# Adafruit_TLC5947.net
KiCad netlist of a schematic drawn in EAGLE
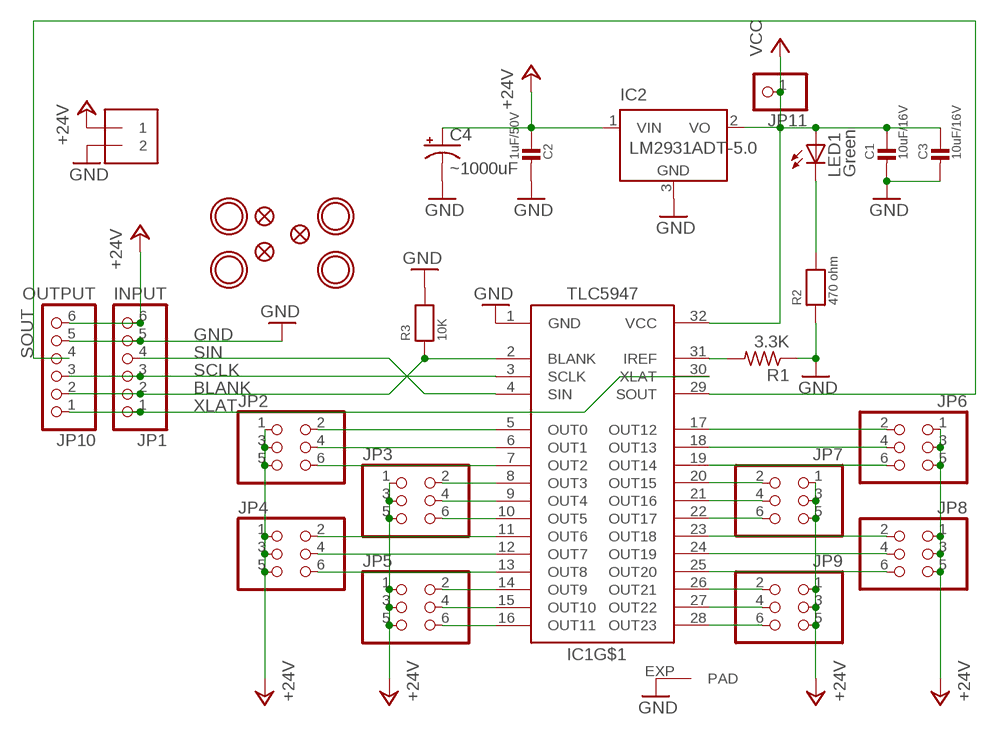
[diagram p0: schematic, sheet 1]

(export (version "E")
  (design (tool "Eeschema 10.0.6"))
  (components
    (comp (ref "C1")
      (value "10uF/16V")
      (footprint "eagle-import:0805")
      (libsource (lib "eagle-import") (part "CAP_CERAMIC0805"))
    )
    (comp (ref "C2")
      (value "1uF/50V")
      (footprint "eagle-import:0805")
      (libsource (lib "eagle-import") (part "CAP_CERAMIC0805"))
    )
    (comp (ref "C3")
      (value "10uF/16V")
      (footprint "eagle-import:0805")
      (libsource (lib "eagle-import") (part "CAP_CERAMIC0805"))
    )
    (comp (ref "C4")
      (value "~1000uF")
      (footprint "eagle-import:E3,5-8")
      (libsource (lib "eagle-import") (part "CPOL-USE3.5-8"))
    )
    (comp (ref "FID1")
      (value "FIDUCIAL\"\"")
      (footprint "eagle-import:FIDUCIAL_1MM")
      (libsource (lib "eagle-import") (part "FIDUCIAL{dblquote}{dblquote}"))
    )
    (comp (ref "FID2")
      (value "FIDUCIAL\"\"")
      (footprint "eagle-import:FIDUCIAL_1MM")
      (libsource (lib "eagle-import") (part "FIDUCIAL{dblquote}{dblquote}"))
    )
    (comp (ref "FID3")
      (value "FIDUCIAL\"\"")
      (footprint "eagle-import:FIDUCIAL_1MM")
      (libsource (lib "eagle-import") (part "FIDUCIAL{dblquote}{dblquote}"))
    )
    (comp (ref "IC1")
      (value "TLC5947-DAP")
      (footprint "eagle-import:HTSSOP32DAP")
      (libsource (lib "eagle-import") (part "TLC5947-DAP"))
    )
    (comp (ref "IC2")
      (value "LM2931ADT-5.0")
      (footprint "eagle-import:TO252")
      (fields (field (name "MPN") "LM2936DT-3.3."))
      (libsource (lib "eagle-import") (part "LM2936?DT-3.3"))
    )
    (comp (ref "J1")
      (value "1X2-3.5MM")
      (footprint "eagle-import:1X2-3.5MM")
      (libsource (lib "eagle-import") (part "1X2-3.5MM"))
    )
    (comp (ref "JP1")
      (value "INPUT")
      (footprint "eagle-import:1X06-CLEANBIG")
      (libsource (lib "eagle-import") (part "PINHD-1X6CB"))
    )
    (comp (ref "JP2")
      (value "HEADER-2X3")
      (footprint "eagle-import:2X03_ROUND_70MIL")
      (libsource (lib "eagle-import") (part "HEADER-2X3"))
    )
    (comp (ref "JP3")
      (value "HEADER-2X3")
      (footprint "eagle-import:2X03_ROUND_70MIL")
      (libsource (lib "eagle-import") (part "HEADER-2X3"))
    )
    (comp (ref "JP4")
      (value "HEADER-2X3")
      (footprint "eagle-import:2X03_ROUND_70MIL")
      (libsource (lib "eagle-import") (part "HEADER-2X3"))
    )
    (comp (ref "JP5")
      (value "HEADER-2X3")
      (footprint "eagle-import:2X03_ROUND_70MIL")
      (libsource (lib "eagle-import") (part "HEADER-2X3"))
    )
    (comp (ref "JP6")
      (value "HEADER-2X3")
      (footprint "eagle-import:2X03_ROUND_70MIL")
      (libsource (lib "eagle-import") (part "HEADER-2X3"))
    )
    (comp (ref "JP7")
      (value "HEADER-2X3")
      (footprint "eagle-import:2X03_ROUND_70MIL")
      (libsource (lib "eagle-import") (part "HEADER-2X3"))
    )
    (comp (ref "JP8")
      (value "HEADER-2X3")
      (footprint "eagle-import:2X03_ROUND_70MIL")
      (libsource (lib "eagle-import") (part "HEADER-2X3"))
    )
    (comp (ref "JP9")
      (value "HEADER-2X3")
      (footprint "eagle-import:2X03_ROUND_70MIL")
      (libsource (lib "eagle-import") (part "HEADER-2X3"))
    )
    (comp (ref "JP10")
      (value "OUTPUT")
      (footprint "eagle-import:1X06-CLEANBIG")
      (libsource (lib "eagle-import") (part "PINHD-1X6CB"))
    )
    (comp (ref "JP11")
      (value "PINHD-1X1CB")
      (footprint "eagle-import:1X01-CLEANBIG")
      (libsource (lib "eagle-import") (part "PINHD-1X1CB"))
    )
    (comp (ref "LED1")
      (value "Green")
      (footprint "eagle-import:CHIP-LED0805")
      (libsource (lib "eagle-import") (part "LEDCHIP-LED0805"))
    )
    (comp (ref "R1")
      (value "3.3K")
      (footprint "eagle-import:0805-THM")
      (libsource (lib "eagle-import") (part "FLIPFLOP-RES"))
    )
    (comp (ref "R2")
      (value "470 ohm")
      (footprint "eagle-import:0805")
      (libsource (lib "eagle-import") (part "RESISTOR0805"))
    )
    (comp (ref "R3")
      (value "10K")
      (footprint "eagle-import:0805")
      (libsource (lib "eagle-import") (part "RESISTOR0805"))
    )
    (comp (ref "U$1")
      (value "MOUNTINGHOLE2.5")
      (footprint "eagle-import:MOUNTINGHOLE_2.5_PLATED")
      (libsource (lib "eagle-import") (part "MOUNTINGHOLE2.5"))
    )
    (comp (ref "U$2")
      (value "MOUNTINGHOLE2.5")
      (footprint "eagle-import:MOUNTINGHOLE_2.5_PLATED")
      (libsource (lib "eagle-import") (part "MOUNTINGHOLE2.5"))
    )
    (comp (ref "U$3")
      (value "MOUNTINGHOLE2.5")
      (footprint "eagle-import:MOUNTINGHOLE_2.5_PLATED")
      (libsource (lib "eagle-import") (part "MOUNTINGHOLE2.5"))
    )
    (comp (ref "U$4")
      (value "MOUNTINGHOLE2.5")
      (footprint "eagle-import:MOUNTINGHOLE_2.5_PLATED")
      (libsource (lib "eagle-import") (part "MOUNTINGHOLE2.5"))
    )
  )
  (nets
    (net (code "1") (name "+24V") (class "Default")
      (node (ref "C2") (pin "1") (pinfunction "P$1_1") (pintype "passive"))
      (node (ref "C4") (pin "+") (pinfunction "+_+") (pintype "passive"))
      (node (ref "IC2") (pin "1") (pinfunction "VIN_1") (pintype "input"))
      (node (ref "J1") (pin "1") (pinfunction "1_1") (pintype "passive"))
      (node (ref "JP1") (pin "6") (pinfunction "6_6") (pintype "passive"))
      (node (ref "JP10") (pin "6") (pinfunction "6_6") (pintype "passive"))
      (node (ref "JP2") (pin "1") (pinfunction "1_1") (pintype "passive"))
      (node (ref "JP2") (pin "3") (pinfunction "3_3") (pintype "passive"))
      (node (ref "JP2") (pin "5") (pinfunction "5_5") (pintype "passive"))
      (node (ref "JP3") (pin "1") (pinfunction "1_1") (pintype "passive"))
      (node (ref "JP3") (pin "3") (pinfunction "3_3") (pintype "passive"))
      (node (ref "JP3") (pin "5") (pinfunction "5_5") (pintype "passive"))
      (node (ref "JP4") (pin "1") (pinfunction "1_1") (pintype "passive"))
      (node (ref "JP4") (pin "3") (pinfunction "3_3") (pintype "passive"))
      (node (ref "JP4") (pin "5") (pinfunction "5_5") (pintype "passive"))
      (node (ref "JP5") (pin "1") (pinfunction "1_1") (pintype "passive"))
      (node (ref "JP5") (pin "3") (pinfunction "3_3") (pintype "passive"))
      (node (ref "JP5") (pin "5") (pinfunction "5_5") (pintype "passive"))
      (node (ref "JP6") (pin "1") (pinfunction "1_1") (pintype "passive"))
      (node (ref "JP6") (pin "3") (pinfunction "3_3") (pintype "passive"))
      (node (ref "JP6") (pin "5") (pinfunction "5_5") (pintype "passive"))
      (node (ref "JP7") (pin "1") (pinfunction "1_1") (pintype "passive"))
      (node (ref "JP7") (pin "3") (pinfunction "3_3") (pintype "passive"))
      (node (ref "JP7") (pin "5") (pinfunction "5_5") (pintype "passive"))
      (node (ref "JP8") (pin "1") (pinfunction "1_1") (pintype "passive"))
      (node (ref "JP8") (pin "3") (pinfunction "3_3") (pintype "passive"))
      (node (ref "JP8") (pin "5") (pinfunction "5_5") (pintype "passive"))
      (node (ref "JP9") (pin "1") (pinfunction "1_1") (pintype "passive"))
      (node (ref "JP9") (pin "3") (pinfunction "3_3") (pintype "passive"))
      (node (ref "JP9") (pin "5") (pinfunction "5_5") (pintype "passive"))
    )
    (net (code "2") (name "/BLANK") (class "Default")
      (node (ref "IC1") (pin "2") (pinfunction "BLANK_2") (pintype "input"))
      (node (ref "JP1") (pin "2") (pinfunction "2_2") (pintype "passive"))
      (node (ref "JP10") (pin "2") (pinfunction "2_2") (pintype "passive"))
      (node (ref "R3") (pin "1") (pinfunction "1_1") (pintype "passive"))
    )
    (net (code "3") (name "/SCLK") (class "Default")
      (node (ref "IC1") (pin "3") (pinfunction "SCLK_3") (pintype "input"))
      (node (ref "JP1") (pin "3") (pinfunction "3_3") (pintype "passive"))
      (node (ref "JP10") (pin "3") (pinfunction "3_3") (pintype "passive"))
    )
    (net (code "4") (name "/SIN") (class "Default")
      (node (ref "IC1") (pin "4") (pinfunction "SIN_4") (pintype "input"))
      (node (ref "JP1") (pin "4") (pinfunction "4_4") (pintype "passive"))
    )
    (net (code "5") (name "/SOUT") (class "Default")
      (node (ref "IC1") (pin "29") (pinfunction "SOUT_29") (pintype "output"))
      (node (ref "JP10") (pin "4") (pinfunction "4_4") (pintype "passive"))
    )
    (net (code "6") (name "/XLAT") (class "Default")
      (node (ref "IC1") (pin "30") (pinfunction "XLAT_30") (pintype "input"))
      (node (ref "JP1") (pin "1") (pinfunction "1_1") (pintype "passive"))
      (node (ref "JP10") (pin "1") (pinfunction "1_1") (pintype "passive"))
    )
    (net (code "7") (name "GND") (class "Default")
      (node (ref "C1") (pin "2") (pinfunction "P$2_2") (pintype "passive"))
      (node (ref "C2") (pin "2") (pinfunction "P$2_2") (pintype "passive"))
      (node (ref "C3") (pin "2") (pinfunction "P$2_2") (pintype "passive"))
      (node (ref "C4") (pin "-") (pinfunction "-_-") (pintype "passive"))
      (node (ref "IC1") (pin "1") (pinfunction "GND_1") (pintype "power_in"))
      (node (ref "IC1") (pin "EXP") (pinfunction "PAD_EXP") (pintype "passive"))
      (node (ref "IC2") (pin "3") (pinfunction "GND_3") (pintype "passive"))
      (node (ref "J1") (pin "2") (pinfunction "2_2") (pintype "passive"))
      (node (ref "JP1") (pin "5") (pinfunction "5_5") (pintype "passive"))
      (node (ref "JP10") (pin "5") (pinfunction "5_5") (pintype "passive"))
      (node (ref "R1") (pin "1") (pinfunction "1_1") (pintype "passive"))
      (node (ref "R2") (pin "1") (pinfunction "1_1") (pintype "passive"))
      (node (ref "R3") (pin "2") (pinfunction "2_2") (pintype "passive"))
    )
    (net (code "8") (name "Net-(IC1A-IREF)") (class "Default")
      (node (ref "IC1") (pin "31") (pinfunction "IREF_31") (pintype "bidirectional"))
      (node (ref "R1") (pin "2") (pinfunction "2_2") (pintype "passive"))
    )
    (net (code "9") (name "Net-(IC1A-OUT0)") (class "Default")
      (node (ref "IC1") (pin "5") (pinfunction "OUT0_5") (pintype "open_collector"))
      (node (ref "JP2") (pin "2") (pinfunction "2_2") (pintype "passive"))
    )
    (net (code "10") (name "Net-(IC1A-OUT1)") (class "Default")
      (node (ref "IC1") (pin "6") (pinfunction "OUT1_6") (pintype "open_collector"))
      (node (ref "JP2") (pin "4") (pinfunction "4_4") (pintype "passive"))
    )
    (net (code "11") (name "Net-(IC1A-OUT2)") (class "Default")
      (node (ref "IC1") (pin "7") (pinfunction "OUT2_7") (pintype "open_collector"))
      (node (ref "JP2") (pin "6") (pinfunction "6_6") (pintype "passive"))
    )
    (net (code "12") (name "Net-(IC1A-OUT3)") (class "Default")
      (node (ref "IC1") (pin "8") (pinfunction "OUT3_8") (pintype "open_collector"))
      (node (ref "JP3") (pin "2") (pinfunction "2_2") (pintype "passive"))
    )
    (net (code "13") (name "Net-(IC1A-OUT4)") (class "Default")
      (node (ref "IC1") (pin "9") (pinfunction "OUT4_9") (pintype "open_collector"))
      (node (ref "JP3") (pin "4") (pinfunction "4_4") (pintype "passive"))
    )
    (net (code "14") (name "Net-(IC1A-OUT5)") (class "Default")
      (node (ref "IC1") (pin "10") (pinfunction "OUT5_10") (pintype "open_collector"))
      (node (ref "JP3") (pin "6") (pinfunction "6_6") (pintype "passive"))
    )
    (net (code "15") (name "Net-(IC1A-OUT6)") (class "Default")
      (node (ref "IC1") (pin "11") (pinfunction "OUT6_11") (pintype "open_collector"))
      (node (ref "JP4") (pin "2") (pinfunction "2_2") (pintype "passive"))
    )
    (net (code "16") (name "Net-(IC1A-OUT7)") (class "Default")
      (node (ref "IC1") (pin "12") (pinfunction "OUT7_12") (pintype "open_collector"))
      (node (ref "JP4") (pin "4") (pinfunction "4_4") (pintype "passive"))
    )
    (net (code "17") (name "Net-(IC1A-OUT8)") (class "Default")
      (node (ref "IC1") (pin "13") (pinfunction "OUT8_13") (pintype "open_collector"))
      (node (ref "JP4") (pin "6") (pinfunction "6_6") (pintype "passive"))
    )
    (net (code "18") (name "Net-(IC1A-OUT9)") (class "Default")
      (node (ref "IC1") (pin "14") (pinfunction "OUT9_14") (pintype "open_collector"))
      (node (ref "JP5") (pin "2") (pinfunction "2_2") (pintype "passive"))
    )
    (net (code "19") (name "Net-(IC1A-OUT10)") (class "Default")
      (node (ref "IC1") (pin "15") (pinfunction "OUT10_15") (pintype "open_collector"))
      (node (ref "JP5") (pin "4") (pinfunction "4_4") (pintype "passive"))
    )
    (net (code "20") (name "Net-(IC1A-OUT11)") (class "Default")
      (node (ref "IC1") (pin "16") (pinfunction "OUT11_16") (pintype "open_collector"))
      (node (ref "JP5") (pin "6") (pinfunction "6_6") (pintype "passive"))
    )
    (net (code "21") (name "Net-(IC1A-OUT12)") (class "Default")
      (node (ref "IC1") (pin "17") (pinfunction "OUT12_17") (pintype "open_collector"))
      (node (ref "JP6") (pin "2") (pinfunction "2_2") (pintype "passive"))
    )
    (net (code "22") (name "Net-(IC1A-OUT13)") (class "Default")
      (node (ref "IC1") (pin "18") (pinfunction "OUT13_18") (pintype "open_collector"))
      (node (ref "JP6") (pin "4") (pinfunction "4_4") (pintype "passive"))
    )
    (net (code "23") (name "Net-(IC1A-OUT14)") (class "Default")
      (node (ref "IC1") (pin "19") (pinfunction "OUT14_19") (pintype "open_collector"))
      (node (ref "JP6") (pin "6") (pinfunction "6_6") (pintype "passive"))
    )
    (net (code "24") (name "Net-(IC1A-OUT15)") (class "Default")
      (node (ref "IC1") (pin "20") (pinfunction "OUT15_20") (pintype "open_collector"))
      (node (ref "JP7") (pin "2") (pinfunction "2_2") (pintype "passive"))
    )
    (net (code "25") (name "Net-(IC1A-OUT16)") (class "Default")
      (node (ref "IC1") (pin "21") (pinfunction "OUT16_21") (pintype "open_collector"))
      (node (ref "JP7") (pin "4") (pinfunction "4_4") (pintype "passive"))
    )
    (net (code "26") (name "Net-(IC1A-OUT17)") (class "Default")
      (node (ref "IC1") (pin "22") (pinfunction "OUT17_22") (pintype "open_collector"))
      (node (ref "JP7") (pin "6") (pinfunction "6_6") (pintype "passive"))
    )
    (net (code "27") (name "Net-(IC1A-OUT18)") (class "Default")
      (node (ref "IC1") (pin "23") (pinfunction "OUT18_23") (pintype "open_collector"))
      (node (ref "JP8") (pin "2") (pinfunction "2_2") (pintype "passive"))
    )
    (net (code "28") (name "Net-(IC1A-OUT19)") (class "Default")
      (node (ref "IC1") (pin "24") (pinfunction "OUT19_24") (pintype "open_collector"))
      (node (ref "JP8") (pin "4") (pinfunction "4_4") (pintype "passive"))
    )
    (net (code "29") (name "Net-(IC1A-OUT20)") (class "Default")
      (node (ref "IC1") (pin "25") (pinfunction "OUT20_25") (pintype "open_collector"))
      (node (ref "JP8") (pin "6") (pinfunction "6_6") (pintype "passive"))
    )
    (net (code "30") (name "Net-(IC1A-OUT21)") (class "Default")
      (node (ref "IC1") (pin "26") (pinfunction "OUT21_26") (pintype "open_collector"))
      (node (ref "JP9") (pin "2") (pinfunction "2_2") (pintype "passive"))
    )
    (net (code "31") (name "Net-(IC1A-OUT22)") (class "Default")
      (node (ref "IC1") (pin "27") (pinfunction "OUT22_27") (pintype "open_collector"))
      (node (ref "JP9") (pin "4") (pinfunction "4_4") (pintype "passive"))
    )
    (net (code "32") (name "Net-(IC1A-OUT23)") (class "Default")
      (node (ref "IC1") (pin "28") (pinfunction "OUT23_28") (pintype "open_collector"))
      (node (ref "JP9") (pin "6") (pinfunction "6_6") (pintype "passive"))
    )
    (net (code "33") (name "Net-(LED1-PadC)") (class "Default")
      (node (ref "LED1") (pin "C") (pinfunction "C_C") (pintype "passive"))
      (node (ref "R2") (pin "2") (pinfunction "2_2") (pintype "passive"))
    )
    (net (code "34") (name "VCC") (class "Default")
      (node (ref "C1") (pin "1") (pinfunction "P$1_1") (pintype "passive"))
      (node (ref "C3") (pin "1") (pinfunction "P$1_1") (pintype "passive"))
      (node (ref "IC1") (pin "32") (pinfunction "VCC_32") (pintype "power_in"))
      (node (ref "IC2") (pin "2") (pinfunction "VO_2") (pintype "passive"))
      (node (ref "JP11") (pin "1") (pinfunction "1_1") (pintype "passive"))
      (node (ref "LED1") (pin "A") (pinfunction "A_A") (pintype "passive"))
    )
  )
)
